# trashotron-driver-v1.net
KiCad netlist of a schematic drawn in EAGLE
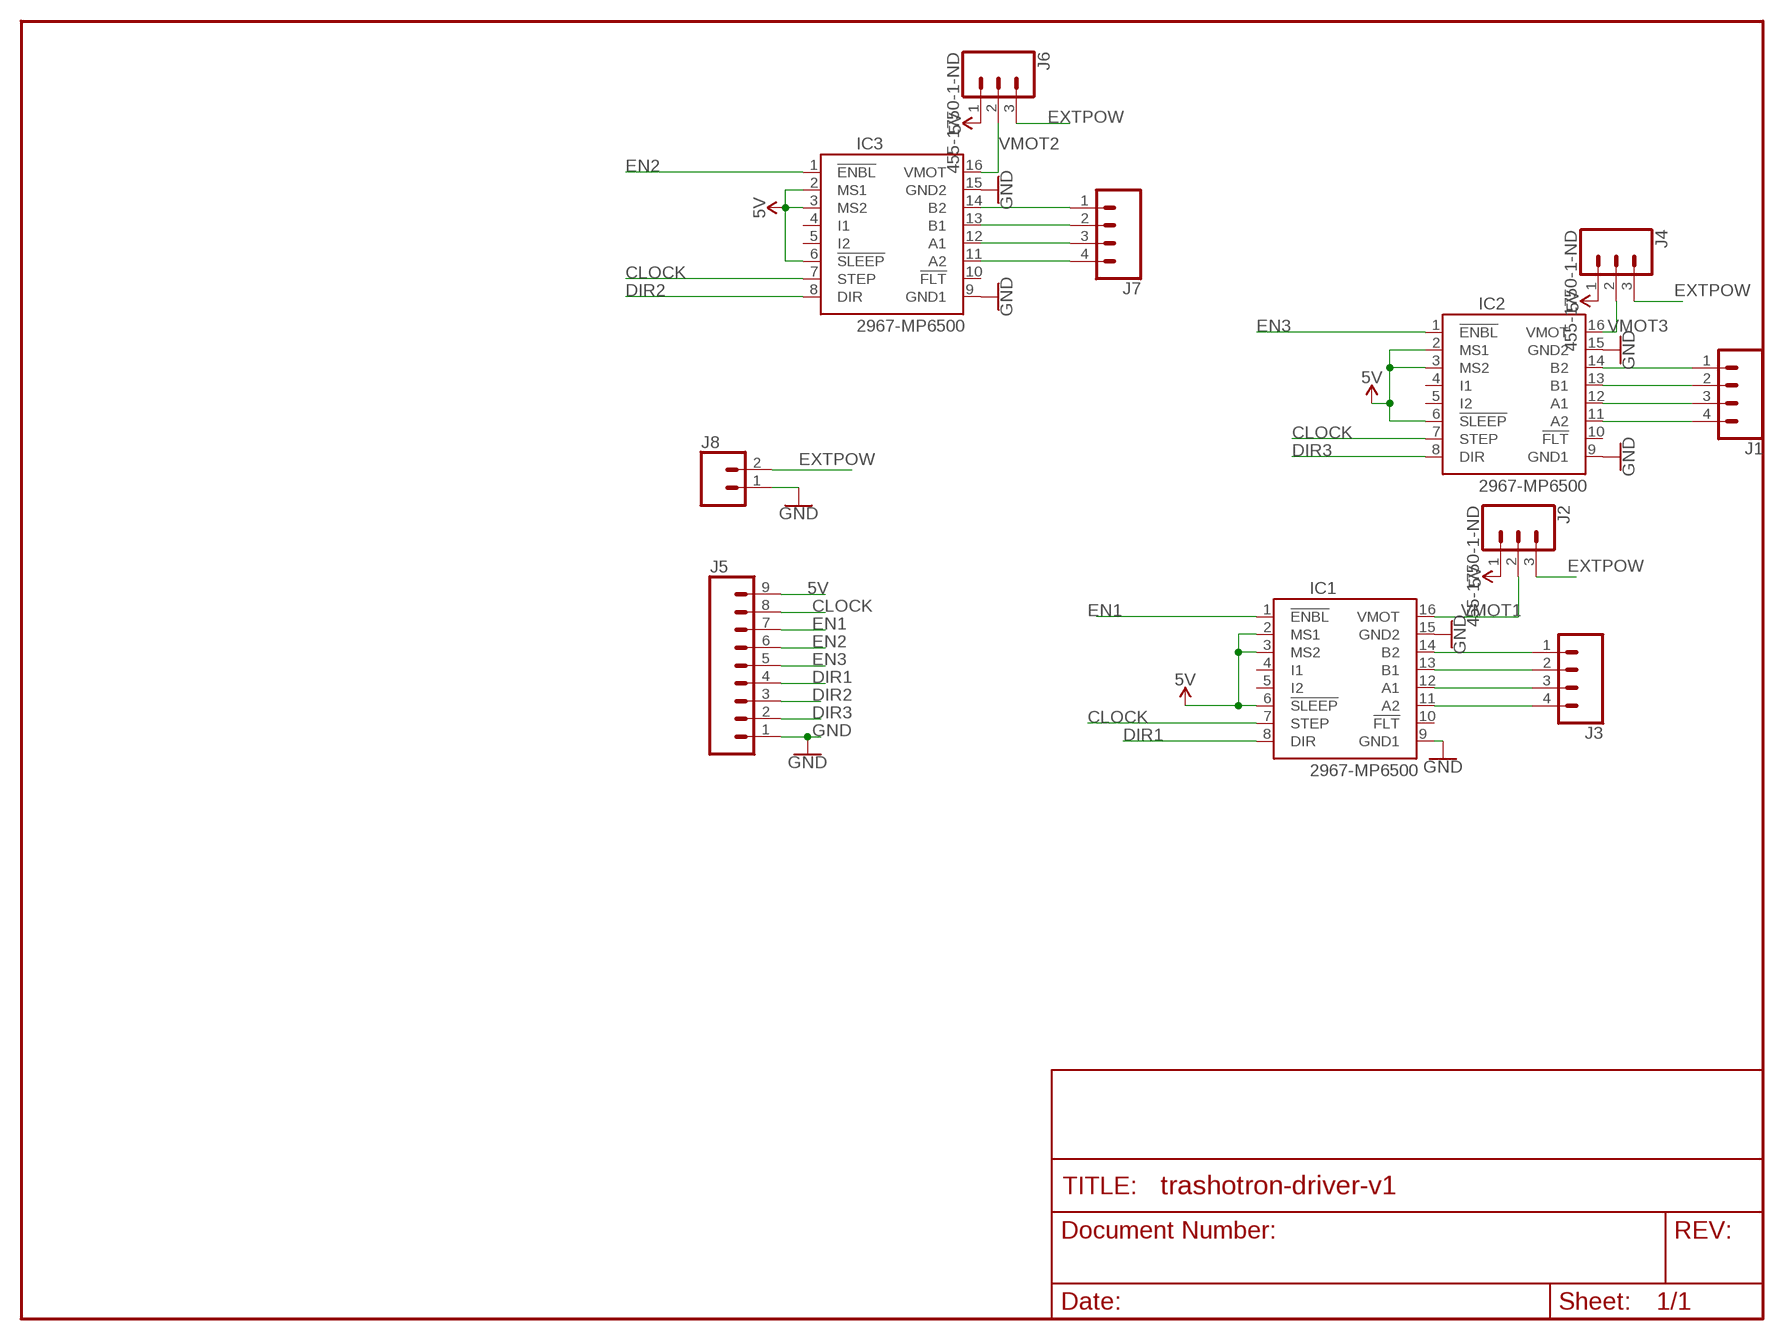
[diagram p0: schematic, sheet 1]

(export (version "E")
  (design (tool "Eeschema 10.0.6"))
  (components
    (comp (ref "IC1")
      (value "2967-MP6500")
      (footprint "eagle-import:MP6500")
      (libsource (lib "eagle-import") (part "2967-MP6500"))
    )
    (comp (ref "IC2")
      (value "2967-MP6500")
      (footprint "eagle-import:MP6500")
      (libsource (lib "eagle-import") (part "2967-MP6500"))
    )
    (comp (ref "IC3")
      (value "2967-MP6500")
      (footprint "eagle-import:MP6500")
      (libsource (lib "eagle-import") (part "2967-MP6500"))
    )
    (comp (ref "J1")
      (value "CONN_04")
      (footprint "eagle-import:1X04")
      (libsource (lib "eagle-import") (part "CONN_04"))
    )
    (comp (ref "J2")
      (value "455-1750-1-ND")
      (footprint "eagle-import:1X03")
      (libsource (lib "eagle-import") (part "CONN_03"))
    )
    (comp (ref "J3")
      (value "CONN_04")
      (footprint "eagle-import:1X04")
      (libsource (lib "eagle-import") (part "CONN_04"))
    )
    (comp (ref "J4")
      (value "455-1750-1-ND")
      (footprint "eagle-import:1X03")
      (libsource (lib "eagle-import") (part "CONN_03"))
    )
    (comp (ref "J5")
      (value "CONN_09")
      (footprint "eagle-import:1X09")
      (libsource (lib "eagle-import") (part "CONN_09"))
    )
    (comp (ref "J6")
      (value "455-1750-1-ND")
      (footprint "eagle-import:1X03")
      (libsource (lib "eagle-import") (part "CONN_03"))
    )
    (comp (ref "J7")
      (value "CONN_04")
      (footprint "eagle-import:1X04")
      (libsource (lib "eagle-import") (part "CONN_04"))
    )
    (comp (ref "J8")
      (value "CONN_02")
      (footprint "eagle-import:1X02")
      (libsource (lib "eagle-import") (part "CONN_02"))
    )
  )
  (nets
    (net (code "1") (name "/CLOCK") (class "Default")
      (node (ref "IC1") (pin "7") (pinfunction "STEP_7") (pintype "input"))
      (node (ref "IC2") (pin "7") (pinfunction "STEP_7") (pintype "input"))
      (node (ref "IC3") (pin "7") (pinfunction "STEP_7") (pintype "input"))
      (node (ref "J5") (pin "8") (pinfunction "8_8") (pintype "passive"))
    )
    (net (code "2") (name "/DIR1") (class "Default")
      (node (ref "IC1") (pin "8") (pinfunction "DIR_8") (pintype "input"))
      (node (ref "J5") (pin "4") (pinfunction "4_4") (pintype "passive"))
    )
    (net (code "3") (name "/DIR2") (class "Default")
      (node (ref "IC3") (pin "8") (pinfunction "DIR_8") (pintype "input"))
      (node (ref "J5") (pin "3") (pinfunction "3_3") (pintype "passive"))
    )
    (net (code "4") (name "/DIR3") (class "Default")
      (node (ref "IC2") (pin "8") (pinfunction "DIR_8") (pintype "input"))
      (node (ref "J5") (pin "2") (pinfunction "2_2") (pintype "passive"))
    )
    (net (code "5") (name "/EN1") (class "Default")
      (node (ref "IC1") (pin "1") (pinfunction "~{ENBL}_1") (pintype "passive"))
      (node (ref "J5") (pin "7") (pinfunction "7_7") (pintype "passive"))
    )
    (net (code "6") (name "/EN2") (class "Default")
      (node (ref "IC3") (pin "1") (pinfunction "~{ENBL}_1") (pintype "passive"))
      (node (ref "J5") (pin "6") (pinfunction "6_6") (pintype "passive"))
    )
    (net (code "7") (name "/EN3") (class "Default")
      (node (ref "IC2") (pin "1") (pinfunction "~{ENBL}_1") (pintype "passive"))
      (node (ref "J5") (pin "5") (pinfunction "5_5") (pintype "passive"))
    )
    (net (code "8") (name "/EXTPOW") (class "Default")
      (node (ref "J2") (pin "3") (pinfunction "3_3") (pintype "passive"))
      (node (ref "J4") (pin "3") (pinfunction "3_3") (pintype "passive"))
      (node (ref "J6") (pin "3") (pinfunction "3_3") (pintype "passive"))
      (node (ref "J8") (pin "2") (pinfunction "2_2") (pintype "passive"))
    )
    (net (code "9") (name "/VMOT1") (class "Default")
      (node (ref "IC1") (pin "16") (pinfunction "VMOT_16") (pintype "power_in"))
      (node (ref "J2") (pin "2") (pinfunction "2_2") (pintype "passive"))
    )
    (net (code "10") (name "/VMOT2") (class "Default")
      (node (ref "IC3") (pin "16") (pinfunction "VMOT_16") (pintype "power_in"))
      (node (ref "J6") (pin "2") (pinfunction "2_2") (pintype "passive"))
    )
    (net (code "11") (name "/VMOT3") (class "Default")
      (node (ref "IC2") (pin "16") (pinfunction "VMOT_16") (pintype "power_in"))
      (node (ref "J4") (pin "2") (pinfunction "2_2") (pintype "passive"))
    )
    (net (code "12") (name "5V") (class "Default")
      (node (ref "IC1") (pin "2") (pinfunction "MS1_2") (pintype "passive"))
      (node (ref "IC1") (pin "3") (pinfunction "MS2_3") (pintype "passive"))
      (node (ref "IC1") (pin "6") (pinfunction "~{SLEEP}_6") (pintype "input"))
      (node (ref "IC2") (pin "2") (pinfunction "MS1_2") (pintype "passive"))
      (node (ref "IC2") (pin "3") (pinfunction "MS2_3") (pintype "passive"))
      (node (ref "IC2") (pin "6") (pinfunction "~{SLEEP}_6") (pintype "input"))
      (node (ref "IC3") (pin "2") (pinfunction "MS1_2") (pintype "passive"))
      (node (ref "IC3") (pin "3") (pinfunction "MS2_3") (pintype "passive"))
      (node (ref "IC3") (pin "6") (pinfunction "~{SLEEP}_6") (pintype "input"))
      (node (ref "J2") (pin "1") (pinfunction "1_1") (pintype "passive"))
      (node (ref "J4") (pin "1") (pinfunction "1_1") (pintype "passive"))
      (node (ref "J5") (pin "9") (pinfunction "9_9") (pintype "passive"))
      (node (ref "J6") (pin "1") (pinfunction "1_1") (pintype "passive"))
    )
    (net (code "13") (name "GND") (class "Default")
      (node (ref "IC1") (pin "15") (pinfunction "GND2_15") (pintype "power_in"))
      (node (ref "IC1") (pin "9") (pinfunction "GND1_9") (pintype "power_in"))
      (node (ref "IC2") (pin "15") (pinfunction "GND2_15") (pintype "power_in"))
      (node (ref "IC2") (pin "9") (pinfunction "GND1_9") (pintype "power_in"))
      (node (ref "IC3") (pin "15") (pinfunction "GND2_15") (pintype "power_in"))
      (node (ref "IC3") (pin "9") (pinfunction "GND1_9") (pintype "power_in"))
      (node (ref "J5") (pin "1") (pinfunction "1_1") (pintype "passive"))
      (node (ref "J8") (pin "1") (pinfunction "1_1") (pintype "passive"))
    )
    (net (code "14") (name "Net-(IC1-A1)") (class "Default")
      (node (ref "IC1") (pin "12") (pinfunction "A1_12") (pintype "output"))
      (node (ref "J3") (pin "3") (pinfunction "3_3") (pintype "passive"))
    )
    (net (code "15") (name "Net-(IC1-A2)") (class "Default")
      (node (ref "IC1") (pin "11") (pinfunction "A2_11") (pintype "output"))
      (node (ref "J3") (pin "4") (pinfunction "4_4") (pintype "passive"))
    )
    (net (code "16") (name "Net-(IC1-B1)") (class "Default")
      (node (ref "IC1") (pin "13") (pinfunction "B1_13") (pintype "output"))
      (node (ref "J3") (pin "2") (pinfunction "2_2") (pintype "passive"))
    )
    (net (code "17") (name "Net-(IC1-B2)") (class "Default")
      (node (ref "IC1") (pin "14") (pinfunction "B2_14") (pintype "output"))
      (node (ref "J3") (pin "1") (pinfunction "1_1") (pintype "passive"))
    )
    (net (code "18") (name "Net-(IC2-A1)") (class "Default")
      (node (ref "IC2") (pin "12") (pinfunction "A1_12") (pintype "output"))
      (node (ref "J1") (pin "3") (pinfunction "3_3") (pintype "passive"))
    )
    (net (code "19") (name "Net-(IC2-A2)") (class "Default")
      (node (ref "IC2") (pin "11") (pinfunction "A2_11") (pintype "output"))
      (node (ref "J1") (pin "4") (pinfunction "4_4") (pintype "passive"))
    )
    (net (code "20") (name "Net-(IC2-B1)") (class "Default")
      (node (ref "IC2") (pin "13") (pinfunction "B1_13") (pintype "output"))
      (node (ref "J1") (pin "2") (pinfunction "2_2") (pintype "passive"))
    )
    (net (code "21") (name "Net-(IC2-B2)") (class "Default")
      (node (ref "IC2") (pin "14") (pinfunction "B2_14") (pintype "output"))
      (node (ref "J1") (pin "1") (pinfunction "1_1") (pintype "passive"))
    )
    (net (code "22") (name "Net-(IC3-A1)") (class "Default")
      (node (ref "IC3") (pin "12") (pinfunction "A1_12") (pintype "output"))
      (node (ref "J7") (pin "3") (pinfunction "3_3") (pintype "passive"))
    )
    (net (code "23") (name "Net-(IC3-A2)") (class "Default")
      (node (ref "IC3") (pin "11") (pinfunction "A2_11") (pintype "output"))
      (node (ref "J7") (pin "4") (pinfunction "4_4") (pintype "passive"))
    )
    (net (code "24") (name "Net-(IC3-B1)") (class "Default")
      (node (ref "IC3") (pin "13") (pinfunction "B1_13") (pintype "output"))
      (node (ref "J7") (pin "2") (pinfunction "2_2") (pintype "passive"))
    )
    (net (code "25") (name "Net-(IC3-B2)") (class "Default")
      (node (ref "IC3") (pin "14") (pinfunction "B2_14") (pintype "output"))
      (node (ref "J7") (pin "1") (pinfunction "1_1") (pintype "passive"))
    )
    (net (code "26") (name "unconnected-(IC1-I1-Pad4)") (class "Default")
      (node (ref "IC1") (pin "4") (pinfunction "I1_4") (pintype "passive"))
    )
    (net (code "27") (name "unconnected-(IC1-I2-Pad5)") (class "Default")
      (node (ref "IC1") (pin "5") (pinfunction "I2_5") (pintype "passive"))
    )
    (net (code "28") (name "unconnected-(IC1-~{FLT}-Pad10)") (class "Default")
      (node (ref "IC1") (pin "10") (pinfunction "~{FLT}_10") (pintype "open_collector"))
    )
    (net (code "29") (name "unconnected-(IC2-I1-Pad4)") (class "Default")
      (node (ref "IC2") (pin "4") (pinfunction "I1_4") (pintype "passive"))
    )
    (net (code "30") (name "unconnected-(IC2-I2-Pad5)") (class "Default")
      (node (ref "IC2") (pin "5") (pinfunction "I2_5") (pintype "passive"))
    )
    (net (code "31") (name "unconnected-(IC2-~{FLT}-Pad10)") (class "Default")
      (node (ref "IC2") (pin "10") (pinfunction "~{FLT}_10") (pintype "open_collector"))
    )
    (net (code "32") (name "unconnected-(IC3-I1-Pad4)") (class "Default")
      (node (ref "IC3") (pin "4") (pinfunction "I1_4") (pintype "passive"))
    )
    (net (code "33") (name "unconnected-(IC3-I2-Pad5)") (class "Default")
      (node (ref "IC3") (pin "5") (pinfunction "I2_5") (pintype "passive"))
    )
    (net (code "34") (name "unconnected-(IC3-~{FLT}-Pad10)") (class "Default")
      (node (ref "IC3") (pin "10") (pinfunction "~{FLT}_10") (pintype "open_collector"))
    )
  )
)
